# new.net
KiCad netlist of a schematic drawn in EAGLE
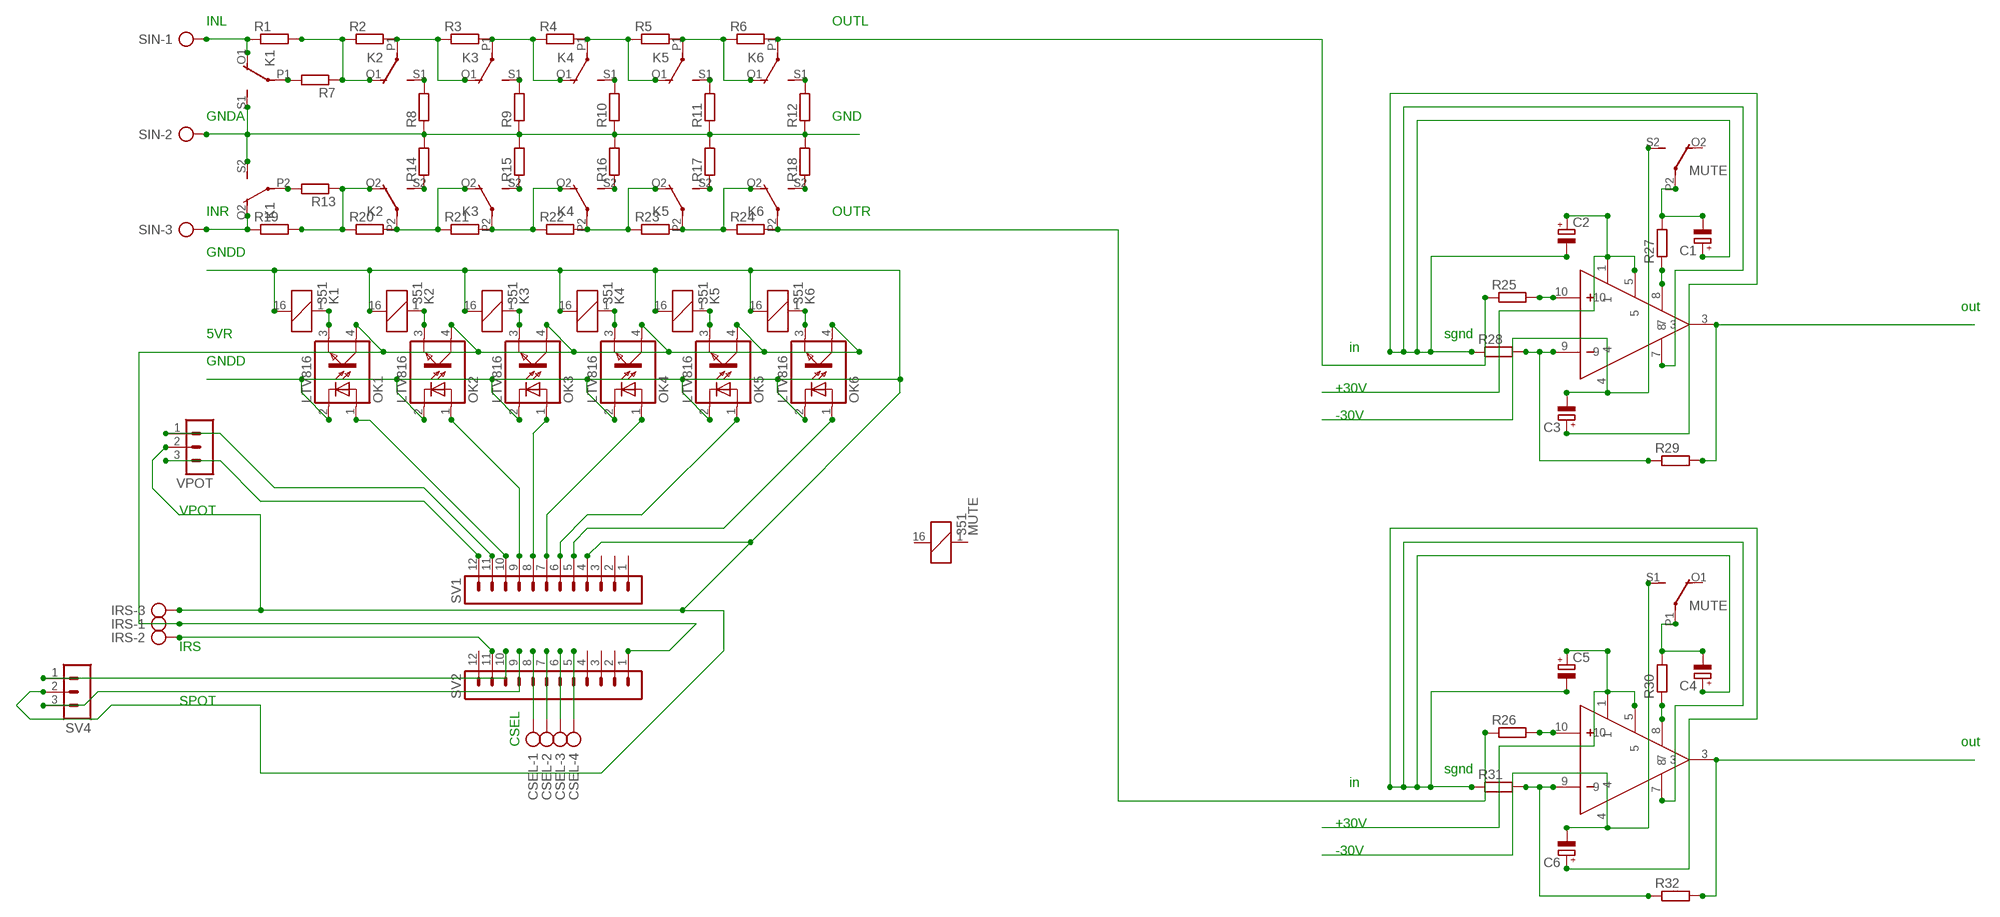
[diagram p0: schematic, sheet 1]

(export (version "E")
  (design (tool "Eeschema 10.0.6"))
  (components
    (comp (ref "C1")
      (value "CPOL-EUE5-13")
      (footprint "eagle-import:E5-13")
      (libsource (lib "eagle-import") (part "CPOL-EUE5-13"))
    )
    (comp (ref "C2")
      (value "CPOL-EUE5-13")
      (footprint "eagle-import:E5-13")
      (libsource (lib "eagle-import") (part "CPOL-EUE5-13"))
    )
    (comp (ref "C3")
      (value "CPOL-EUE5-13")
      (footprint "eagle-import:E5-13")
      (libsource (lib "eagle-import") (part "CPOL-EUE5-13"))
    )
    (comp (ref "C4")
      (value "CPOL-EUE5-13")
      (footprint "eagle-import:E5-13")
      (libsource (lib "eagle-import") (part "CPOL-EUE5-13"))
    )
    (comp (ref "C5")
      (value "CPOL-EUE5-13")
      (footprint "eagle-import:E5-13")
      (libsource (lib "eagle-import") (part "CPOL-EUE5-13"))
    )
    (comp (ref "C6")
      (value "CPOL-EUE5-13")
      (footprint "eagle-import:E5-13")
      (libsource (lib "eagle-import") (part "CPOL-EUE5-13"))
    )
    (comp (ref "CSEL")
      (value "AK500/4")
      (footprint "eagle-import:AK500_4")
      (libsource (lib "eagle-import") (part "AK500/4"))
    )
    (comp (ref "IRS")
      (value "AK500/3")
      (footprint "eagle-import:AK500_3")
      (libsource (lib "eagle-import") (part "AK500/3"))
    )
    (comp (ref "K1")
      (value "351")
      (footprint "eagle-import:351")
      (libsource (lib "eagle-import") (part "351"))
    )
    (comp (ref "K2")
      (value "351")
      (footprint "eagle-import:351")
      (libsource (lib "eagle-import") (part "351"))
    )
    (comp (ref "K3")
      (value "351")
      (footprint "eagle-import:351")
      (libsource (lib "eagle-import") (part "351"))
    )
    (comp (ref "K4")
      (value "351")
      (footprint "eagle-import:351")
      (libsource (lib "eagle-import") (part "351"))
    )
    (comp (ref "K5")
      (value "351")
      (footprint "eagle-import:351")
      (libsource (lib "eagle-import") (part "351"))
    )
    (comp (ref "K6")
      (value "351")
      (footprint "eagle-import:351")
      (libsource (lib "eagle-import") (part "351"))
    )
    (comp (ref "MUTE")
      (value "351")
      (footprint "eagle-import:351")
      (libsource (lib "eagle-import") (part "351"))
    )
    (comp (ref "OK1")
      (value "LTV816")
      (footprint "eagle-import:DIL04")
      (libsource (lib "eagle-import") (part "LTV816"))
    )
    (comp (ref "OK2")
      (value "LTV816")
      (footprint "eagle-import:DIL04")
      (libsource (lib "eagle-import") (part "LTV816"))
    )
    (comp (ref "OK3")
      (value "LTV816")
      (footprint "eagle-import:DIL04")
      (libsource (lib "eagle-import") (part "LTV816"))
    )
    (comp (ref "OK4")
      (value "LTV816")
      (footprint "eagle-import:DIL04")
      (libsource (lib "eagle-import") (part "LTV816"))
    )
    (comp (ref "OK5")
      (value "LTV816")
      (footprint "eagle-import:DIL04")
      (libsource (lib "eagle-import") (part "LTV816"))
    )
    (comp (ref "OK6")
      (value "LTV816")
      (footprint "eagle-import:DIL04")
      (libsource (lib "eagle-import") (part "LTV816"))
    )
    (comp (ref "R1")
      (value "R-EU_0204/7")
      (footprint "eagle-import:0204_7")
      (libsource (lib "eagle-import") (part "R-EU_0204/7"))
    )
    (comp (ref "R2")
      (value "R-EU_0204/7")
      (footprint "eagle-import:0204_7")
      (libsource (lib "eagle-import") (part "R-EU_0204/7"))
    )
    (comp (ref "R3")
      (value "R-EU_0204/7")
      (footprint "eagle-import:0204_7")
      (libsource (lib "eagle-import") (part "R-EU_0204/7"))
    )
    (comp (ref "R4")
      (value "R-EU_0204/7")
      (footprint "eagle-import:0204_7")
      (libsource (lib "eagle-import") (part "R-EU_0204/7"))
    )
    (comp (ref "R5")
      (value "R-EU_0204/7")
      (footprint "eagle-import:0204_7")
      (libsource (lib "eagle-import") (part "R-EU_0204/7"))
    )
    (comp (ref "R6")
      (value "R-EU_0204/7")
      (footprint "eagle-import:0204_7")
      (libsource (lib "eagle-import") (part "R-EU_0204/7"))
    )
    (comp (ref "R7")
      (value "R-EU_0204/7")
      (footprint "eagle-import:0204_7")
      (libsource (lib "eagle-import") (part "R-EU_0204/7"))
    )
    (comp (ref "R8")
      (value "R-EU_0204/7")
      (footprint "eagle-import:0204_7")
      (libsource (lib "eagle-import") (part "R-EU_0204/7"))
    )
    (comp (ref "R9")
      (value "R-EU_0204/7")
      (footprint "eagle-import:0204_7")
      (libsource (lib "eagle-import") (part "R-EU_0204/7"))
    )
    (comp (ref "R10")
      (value "R-EU_0204/7")
      (footprint "eagle-import:0204_7")
      (libsource (lib "eagle-import") (part "R-EU_0204/7"))
    )
    (comp (ref "R11")
      (value "R-EU_0204/7")
      (footprint "eagle-import:0204_7")
      (libsource (lib "eagle-import") (part "R-EU_0204/7"))
    )
    (comp (ref "R12")
      (value "R-EU_0204/7")
      (footprint "eagle-import:0204_7")
      (libsource (lib "eagle-import") (part "R-EU_0204/7"))
    )
    (comp (ref "R13")
      (value "R-EU_0204/7")
      (footprint "eagle-import:0204_7")
      (libsource (lib "eagle-import") (part "R-EU_0204/7"))
    )
    (comp (ref "R14")
      (value "R-EU_0204/7")
      (footprint "eagle-import:0204_7")
      (libsource (lib "eagle-import") (part "R-EU_0204/7"))
    )
    (comp (ref "R15")
      (value "R-EU_0204/7")
      (footprint "eagle-import:0204_7")
      (libsource (lib "eagle-import") (part "R-EU_0204/7"))
    )
    (comp (ref "R16")
      (value "R-EU_0204/7")
      (footprint "eagle-import:0204_7")
      (libsource (lib "eagle-import") (part "R-EU_0204/7"))
    )
    (comp (ref "R17")
      (value "R-EU_0204/7")
      (footprint "eagle-import:0204_7")
      (libsource (lib "eagle-import") (part "R-EU_0204/7"))
    )
    (comp (ref "R18")
      (value "R-EU_0204/7")
      (footprint "eagle-import:0204_7")
      (libsource (lib "eagle-import") (part "R-EU_0204/7"))
    )
    (comp (ref "R19")
      (value "R-EU_0204/7")
      (footprint "eagle-import:0204_7")
      (libsource (lib "eagle-import") (part "R-EU_0204/7"))
    )
    (comp (ref "R20")
      (value "R-EU_0204/7")
      (footprint "eagle-import:0204_7")
      (libsource (lib "eagle-import") (part "R-EU_0204/7"))
    )
    (comp (ref "R21")
      (value "R-EU_0204/7")
      (footprint "eagle-import:0204_7")
      (libsource (lib "eagle-import") (part "R-EU_0204/7"))
    )
    (comp (ref "R22")
      (value "R-EU_0204/7")
      (footprint "eagle-import:0204_7")
      (libsource (lib "eagle-import") (part "R-EU_0204/7"))
    )
    (comp (ref "R23")
      (value "R-EU_0204/7")
      (footprint "eagle-import:0204_7")
      (libsource (lib "eagle-import") (part "R-EU_0204/7"))
    )
    (comp (ref "R24")
      (value "R-EU_0204/7")
      (footprint "eagle-import:0204_7")
      (libsource (lib "eagle-import") (part "R-EU_0204/7"))
    )
    (comp (ref "R25")
      (value "R-EU_0207/10")
      (footprint "eagle-import:0207_10")
      (libsource (lib "eagle-import") (part "R-EU_0207/10"))
    )
    (comp (ref "R26")
      (value "R-EU_0207/10")
      (footprint "eagle-import:0207_10")
      (libsource (lib "eagle-import") (part "R-EU_0207/10"))
    )
    (comp (ref "R27")
      (value "R-EU_0207/10")
      (footprint "eagle-import:0207_10")
      (libsource (lib "eagle-import") (part "R-EU_0207/10"))
    )
    (comp (ref "R28")
      (value "R-EU_0207/10")
      (footprint "eagle-import:0207_10")
      (libsource (lib "eagle-import") (part "R-EU_0207/10"))
    )
    (comp (ref "R29")
      (value "R-EU_0207/10")
      (footprint "eagle-import:0207_10")
      (libsource (lib "eagle-import") (part "R-EU_0207/10"))
    )
    (comp (ref "R30")
      (value "R-EU_0207/10")
      (footprint "eagle-import:0207_10")
      (libsource (lib "eagle-import") (part "R-EU_0207/10"))
    )
    (comp (ref "R31")
      (value "R-EU_0207/10")
      (footprint "eagle-import:0207_10")
      (libsource (lib "eagle-import") (part "R-EU_0207/10"))
    )
    (comp (ref "R32")
      (value "R-EU_0207/10")
      (footprint "eagle-import:0207_10")
      (libsource (lib "eagle-import") (part "R-EU_0207/10"))
    )
    (comp (ref "SIN")
      (value "AK500/3")
      (footprint "eagle-import:AK500_3")
      (libsource (lib "eagle-import") (part "AK500/3"))
    )
    (comp (ref "SV1")
      (value "MA12-1")
      (footprint "eagle-import:MA12-1")
      (libsource (lib "eagle-import") (part "MA12-1"))
    )
    (comp (ref "SV2")
      (value "MA12-1")
      (footprint "eagle-import:MA12-1")
      (libsource (lib "eagle-import") (part "MA12-1"))
    )
    (comp (ref "SV4")
      (value "MA03-1")
      (footprint "eagle-import:MA03-1")
      (libsource (lib "eagle-import") (part "MA03-1"))
    )
    (comp (ref "U$1")
      (value "LM3886T")
      (footprint "eagle-import:TO220-11")
      (libsource (lib "eagle-import") (part "LM3886T"))
    )
    (comp (ref "U$2")
      (value "LM3886T")
      (footprint "eagle-import:TO220-11")
      (libsource (lib "eagle-import") (part "LM3886T"))
    )
    (comp (ref "VPOT")
      (value "MA03-1")
      (footprint "eagle-import:MA03-1")
      (libsource (lib "eagle-import") (part "MA03-1"))
    )
  )
  (nets
    (net (code "1") (name "/GNDA") (class "Default")
      (node (ref "C1") (pin "+") (pinfunction "+_+") (pintype "passive"))
      (node (ref "C2") (pin "-") (pinfunction "-_-") (pintype "passive"))
      (node (ref "C3") (pin "+") (pinfunction "+_+") (pintype "passive"))
      (node (ref "C4") (pin "+") (pinfunction "+_+") (pintype "passive"))
      (node (ref "C5") (pin "-") (pinfunction "-_-") (pintype "passive"))
      (node (ref "C6") (pin "+") (pinfunction "+_+") (pintype "passive"))
      (node (ref "K1") (pin "S1") (pinfunction "S_S1") (pintype "passive"))
      (node (ref "K1") (pin "S2") (pinfunction "S_S2") (pintype "passive"))
      (node (ref "R10") (pin "1") (pinfunction "1_1") (pintype "passive"))
      (node (ref "R11") (pin "1") (pinfunction "1_1") (pintype "passive"))
      (node (ref "R12") (pin "1") (pinfunction "1_1") (pintype "passive"))
      (node (ref "R14") (pin "2") (pinfunction "2_2") (pintype "passive"))
      (node (ref "R15") (pin "2") (pinfunction "2_2") (pintype "passive"))
      (node (ref "R16") (pin "2") (pinfunction "2_2") (pintype "passive"))
      (node (ref "R17") (pin "2") (pinfunction "2_2") (pintype "passive"))
      (node (ref "R18") (pin "2") (pinfunction "2_2") (pintype "passive"))
      (node (ref "R28") (pin "1") (pinfunction "1_1") (pintype "passive"))
      (node (ref "R31") (pin "1") (pinfunction "1_1") (pintype "passive"))
      (node (ref "R8") (pin "1") (pinfunction "1_1") (pintype "passive"))
      (node (ref "R9") (pin "1") (pinfunction "1_1") (pintype "passive"))
      (node (ref "SIN") (pin "2") (pinfunction "KL_2") (pintype "passive"))
      (node (ref "U$1") (pin "7") (pinfunction "7_7") (pintype "power_in"))
      (node (ref "U$2") (pin "7") (pinfunction "7_7") (pintype "power_in"))
    )
    (net (code "2") (name "Net-(C2-Pad+)") (class "Default")
      (node (ref "C2") (pin "+") (pinfunction "+_+") (pintype "passive"))
      (node (ref "U$1") (pin "1") (pinfunction "1_1") (pintype "power_in"))
      (node (ref "U$1") (pin "5") (pinfunction "5_5") (pintype "power_in"))
    )
    (net (code "3") (name "Net-(C5-Pad+)") (class "Default")
      (node (ref "C5") (pin "+") (pinfunction "+_+") (pintype "passive"))
      (node (ref "U$2") (pin "1") (pinfunction "1_1") (pintype "power_in"))
      (node (ref "U$2") (pin "5") (pinfunction "5_5") (pintype "power_in"))
    )
    (net (code "4") (name "Net-(CSELA-KL)") (class "Default")
      (node (ref "CSEL") (pin "1") (pinfunction "KL_1") (pintype "passive"))
      (node (ref "SV2") (pin "8") (pinfunction "8_8") (pintype "passive"))
    )
    (net (code "5") (name "Net-(CSELB-KL)") (class "Default")
      (node (ref "CSEL") (pin "2") (pinfunction "KL_2") (pintype "passive"))
      (node (ref "SV2") (pin "7") (pinfunction "7_7") (pintype "passive"))
    )
    (net (code "6") (name "Net-(CSELC-KL)") (class "Default")
      (node (ref "CSEL") (pin "3") (pinfunction "KL_3") (pintype "passive"))
      (node (ref "SV2") (pin "6") (pinfunction "6_6") (pintype "passive"))
    )
    (net (code "7") (name "Net-(CSELD-KL)") (class "Default")
      (node (ref "CSEL") (pin "4") (pinfunction "KL_4") (pintype "passive"))
      (node (ref "SV2") (pin "5") (pinfunction "5_5") (pintype "passive"))
    )
    (net (code "8") (name "Net-(IRSA-KL)") (class "Default")
      (node (ref "IRS") (pin "1") (pinfunction "KL_1") (pintype "passive"))
      (node (ref "OK1") (pin "4") (pinfunction "COL_4") (pintype "passive"))
      (node (ref "OK2") (pin "4") (pinfunction "COL_4") (pintype "passive"))
      (node (ref "OK3") (pin "4") (pinfunction "COL_4") (pintype "passive"))
      (node (ref "OK4") (pin "4") (pinfunction "COL_4") (pintype "passive"))
      (node (ref "OK5") (pin "4") (pinfunction "COL_4") (pintype "passive"))
      (node (ref "OK6") (pin "4") (pinfunction "COL_4") (pintype "passive"))
      (node (ref "SV2") (pin "1") (pinfunction "1_1") (pintype "passive"))
    )
    (net (code "9") (name "Net-(IRSB-KL)") (class "Default")
      (node (ref "IRS") (pin "2") (pinfunction "KL_2") (pintype "passive"))
      (node (ref "SV2") (pin "11") (pinfunction "11_11") (pintype "passive"))
    )
    (net (code "10") (name "Net-(IRSC-KL)") (class "Default")
      (node (ref "IRS") (pin "3") (pinfunction "KL_3") (pintype "passive"))
      (node (ref "K1") (pin "16") (pinfunction "2_16") (pintype "passive"))
      (node (ref "K2") (pin "16") (pinfunction "2_16") (pintype "passive"))
      (node (ref "K3") (pin "16") (pinfunction "2_16") (pintype "passive"))
      (node (ref "K4") (pin "16") (pinfunction "2_16") (pintype "passive"))
      (node (ref "K5") (pin "16") (pinfunction "2_16") (pintype "passive"))
      (node (ref "K6") (pin "16") (pinfunction "2_16") (pintype "passive"))
      (node (ref "OK1") (pin "2") (pinfunction "C_2") (pintype "passive"))
      (node (ref "OK2") (pin "2") (pinfunction "C_2") (pintype "passive"))
      (node (ref "OK3") (pin "2") (pinfunction "C_2") (pintype "passive"))
      (node (ref "OK4") (pin "2") (pinfunction "C_2") (pintype "passive"))
      (node (ref "OK5") (pin "2") (pinfunction "C_2") (pintype "passive"))
      (node (ref "OK6") (pin "2") (pinfunction "C_2") (pintype "passive"))
      (node (ref "SV1") (pin "4") (pinfunction "4_4") (pintype "passive"))
      (node (ref "SV4") (pin "2") (pinfunction "2_2") (pintype "passive"))
      (node (ref "VPOT") (pin "2") (pinfunction "2_2") (pintype "passive"))
    )
    (net (code "11") (name "Net-(K1B-O)") (class "Default")
      (node (ref "K1") (pin "O1") (pinfunction "O_O1") (pintype "passive"))
      (node (ref "R1") (pin "1") (pinfunction "1_1") (pintype "passive"))
      (node (ref "SIN") (pin "1") (pinfunction "KL_1") (pintype "passive"))
    )
    (net (code "12") (name "Net-(K1B-P)") (class "Default")
      (node (ref "K1") (pin "P1") (pinfunction "P_P1") (pintype "passive"))
      (node (ref "R7") (pin "2") (pinfunction "2_2") (pintype "passive"))
    )
    (net (code "13") (name "Net-(K1C-O)") (class "Default")
      (node (ref "K1") (pin "O2") (pinfunction "O_O2") (pintype "passive"))
      (node (ref "R19") (pin "1") (pinfunction "1_1") (pintype "passive"))
      (node (ref "SIN") (pin "3") (pinfunction "KL_3") (pintype "passive"))
    )
    (net (code "14") (name "Net-(K1C-P)") (class "Default")
      (node (ref "K1") (pin "P2") (pinfunction "P_P2") (pintype "passive"))
      (node (ref "R13") (pin "2") (pinfunction "2_2") (pintype "passive"))
    )
    (net (code "15") (name "Net-(K2B-O)") (class "Default")
      (node (ref "K2") (pin "O1") (pinfunction "O_O1") (pintype "passive"))
      (node (ref "R1") (pin "2") (pinfunction "2_2") (pintype "passive"))
      (node (ref "R2") (pin "1") (pinfunction "1_1") (pintype "passive"))
      (node (ref "R7") (pin "1") (pinfunction "1_1") (pintype "passive"))
    )
    (net (code "16") (name "Net-(K2B-P)") (class "Default")
      (node (ref "K2") (pin "P1") (pinfunction "P_P1") (pintype "passive"))
      (node (ref "K3") (pin "O1") (pinfunction "O_O1") (pintype "passive"))
      (node (ref "R2") (pin "2") (pinfunction "2_2") (pintype "passive"))
      (node (ref "R3") (pin "1") (pinfunction "1_1") (pintype "passive"))
    )
    (net (code "17") (name "Net-(K2B-S)") (class "Default")
      (node (ref "K2") (pin "S1") (pinfunction "S_S1") (pintype "passive"))
      (node (ref "R8") (pin "2") (pinfunction "2_2") (pintype "passive"))
    )
    (net (code "18") (name "Net-(K2C-O)") (class "Default")
      (node (ref "K2") (pin "O2") (pinfunction "O_O2") (pintype "passive"))
      (node (ref "R13") (pin "1") (pinfunction "1_1") (pintype "passive"))
      (node (ref "R19") (pin "2") (pinfunction "2_2") (pintype "passive"))
      (node (ref "R20") (pin "1") (pinfunction "1_1") (pintype "passive"))
    )
    (net (code "19") (name "Net-(K2C-P)") (class "Default")
      (node (ref "K2") (pin "P2") (pinfunction "P_P2") (pintype "passive"))
      (node (ref "K3") (pin "O2") (pinfunction "O_O2") (pintype "passive"))
      (node (ref "R20") (pin "2") (pinfunction "2_2") (pintype "passive"))
      (node (ref "R21") (pin "1") (pinfunction "1_1") (pintype "passive"))
    )
    (net (code "20") (name "Net-(K2C-S)") (class "Default")
      (node (ref "K2") (pin "S2") (pinfunction "S_S2") (pintype "passive"))
      (node (ref "R14") (pin "1") (pinfunction "1_1") (pintype "passive"))
    )
    (net (code "21") (name "Net-(K3B-P)") (class "Default")
      (node (ref "K3") (pin "P1") (pinfunction "P_P1") (pintype "passive"))
      (node (ref "K4") (pin "O1") (pinfunction "O_O1") (pintype "passive"))
      (node (ref "R3") (pin "2") (pinfunction "2_2") (pintype "passive"))
      (node (ref "R4") (pin "1") (pinfunction "1_1") (pintype "passive"))
    )
    (net (code "22") (name "Net-(K3B-S)") (class "Default")
      (node (ref "K3") (pin "S1") (pinfunction "S_S1") (pintype "passive"))
      (node (ref "R9") (pin "2") (pinfunction "2_2") (pintype "passive"))
    )
    (net (code "23") (name "Net-(K3C-P)") (class "Default")
      (node (ref "K3") (pin "P2") (pinfunction "P_P2") (pintype "passive"))
      (node (ref "K4") (pin "O2") (pinfunction "O_O2") (pintype "passive"))
      (node (ref "R21") (pin "2") (pinfunction "2_2") (pintype "passive"))
      (node (ref "R22") (pin "1") (pinfunction "1_1") (pintype "passive"))
    )
    (net (code "24") (name "Net-(K3C-S)") (class "Default")
      (node (ref "K3") (pin "S2") (pinfunction "S_S2") (pintype "passive"))
      (node (ref "R15") (pin "1") (pinfunction "1_1") (pintype "passive"))
    )
    (net (code "25") (name "Net-(K4B-P)") (class "Default")
      (node (ref "K4") (pin "P1") (pinfunction "P_P1") (pintype "passive"))
      (node (ref "K5") (pin "O1") (pinfunction "O_O1") (pintype "passive"))
      (node (ref "R4") (pin "2") (pinfunction "2_2") (pintype "passive"))
      (node (ref "R5") (pin "1") (pinfunction "1_1") (pintype "passive"))
    )
    (net (code "26") (name "Net-(K4B-S)") (class "Default")
      (node (ref "K4") (pin "S1") (pinfunction "S_S1") (pintype "passive"))
      (node (ref "R10") (pin "2") (pinfunction "2_2") (pintype "passive"))
    )
    (net (code "27") (name "Net-(K4C-P)") (class "Default")
      (node (ref "K4") (pin "P2") (pinfunction "P_P2") (pintype "passive"))
      (node (ref "K5") (pin "O2") (pinfunction "O_O2") (pintype "passive"))
      (node (ref "R22") (pin "2") (pinfunction "2_2") (pintype "passive"))
      (node (ref "R23") (pin "1") (pinfunction "1_1") (pintype "passive"))
    )
    (net (code "28") (name "Net-(K4C-S)") (class "Default")
      (node (ref "K4") (pin "S2") (pinfunction "S_S2") (pintype "passive"))
      (node (ref "R16") (pin "1") (pinfunction "1_1") (pintype "passive"))
    )
    (net (code "29") (name "Net-(K5B-P)") (class "Default")
      (node (ref "K5") (pin "P1") (pinfunction "P_P1") (pintype "passive"))
      (node (ref "K6") (pin "O1") (pinfunction "O_O1") (pintype "passive"))
      (node (ref "R5") (pin "2") (pinfunction "2_2") (pintype "passive"))
      (node (ref "R6") (pin "1") (pinfunction "1_1") (pintype "passive"))
    )
    (net (code "30") (name "Net-(K5B-S)") (class "Default")
      (node (ref "K5") (pin "S1") (pinfunction "S_S1") (pintype "passive"))
      (node (ref "R11") (pin "2") (pinfunction "2_2") (pintype "passive"))
    )
    (net (code "31") (name "Net-(K5C-P)") (class "Default")
      (node (ref "K5") (pin "P2") (pinfunction "P_P2") (pintype "passive"))
      (node (ref "K6") (pin "O2") (pinfunction "O_O2") (pintype "passive"))
      (node (ref "R23") (pin "2") (pinfunction "2_2") (pintype "passive"))
      (node (ref "R24") (pin "1") (pinfunction "1_1") (pintype "passive"))
    )
    (net (code "32") (name "Net-(K5C-S)") (class "Default")
      (node (ref "K5") (pin "S2") (pinfunction "S_S2") (pintype "passive"))
      (node (ref "R17") (pin "1") (pinfunction "1_1") (pintype "passive"))
    )
    (net (code "33") (name "Net-(K6B-P)") (class "Default")
      (node (ref "K6") (pin "P1") (pinfunction "P_P1") (pintype "passive"))
      (node (ref "R25") (pin "1") (pinfunction "1_1") (pintype "passive"))
      (node (ref "R6") (pin "2") (pinfunction "2_2") (pintype "passive"))
    )
    (net (code "34") (name "Net-(K6B-S)") (class "Default")
      (node (ref "K6") (pin "S1") (pinfunction "S_S1") (pintype "passive"))
      (node (ref "R12") (pin "2") (pinfunction "2_2") (pintype "passive"))
    )
    (net (code "35") (name "Net-(K6C-P)") (class "Default")
      (node (ref "K6") (pin "P2") (pinfunction "P_P2") (pintype "passive"))
      (node (ref "R24") (pin "2") (pinfunction "2_2") (pintype "passive"))
      (node (ref "R26") (pin "1") (pinfunction "1_1") (pintype "passive"))
    )
    (net (code "36") (name "Net-(K6C-S)") (class "Default")
      (node (ref "K6") (pin "S2") (pinfunction "S_S2") (pintype "passive"))
      (node (ref "R18") (pin "1") (pinfunction "1_1") (pintype "passive"))
    )
    (net (code "37") (name "Net-(MUTEB-P)") (class "Default")
      (node (ref "C4") (pin "-") (pinfunction "-_-") (pintype "passive"))
      (node (ref "MUTE") (pin "P1") (pinfunction "P_P1") (pintype "passive"))
      (node (ref "R30") (pin "2") (pinfunction "2_2") (pintype "passive"))
    )
    (net (code "38") (name "Net-(MUTEB-S)") (class "Default")
      (node (ref "C6") (pin "-") (pinfunction "-_-") (pintype "passive"))
      (node (ref "MUTE") (pin "S1") (pinfunction "S_S1") (pintype "passive"))
      (node (ref "U$2") (pin "4") (pinfunction "4_4") (pintype "power_in"))
    )
    (net (code "39") (name "Net-(MUTEC-P)") (class "Default")
      (node (ref "C1") (pin "-") (pinfunction "-_-") (pintype "passive"))
      (node (ref "MUTE") (pin "P2") (pinfunction "P_P2") (pintype "passive"))
      (node (ref "R27") (pin "2") (pinfunction "2_2") (pintype "passive"))
    )
    (net (code "40") (name "Net-(MUTEC-S)") (class "Default")
      (node (ref "C3") (pin "-") (pinfunction "-_-") (pintype "passive"))
      (node (ref "MUTE") (pin "S2") (pinfunction "S_S2") (pintype "passive"))
      (node (ref "U$1") (pin "4") (pinfunction "4_4") (pintype "power_in"))
    )
    (net (code "41") (name "Net-(OK1-A)") (class "Default")
      (node (ref "OK1") (pin "1") (pinfunction "A_1") (pintype "passive"))
      (node (ref "SV1") (pin "10") (pinfunction "10_10") (pintype "passive"))
    )
    (net (code "42") (name "Net-(OK1-EMIT)") (class "Default")
      (node (ref "K1") (pin "1") (pinfunction "1_1") (pintype "passive"))
      (node (ref "OK1") (pin "3") (pinfunction "EMIT_3") (pintype "passive"))
    )
    (net (code "43") (name "Net-(OK2-A)") (class "Default")
      (node (ref "OK2") (pin "1") (pinfunction "A_1") (pintype "passive"))
      (node (ref "SV1") (pin "9") (pinfunction "9_9") (pintype "passive"))
    )
    (net (code "44") (name "Net-(OK2-EMIT)") (class "Default")
      (node (ref "K2") (pin "1") (pinfunction "1_1") (pintype "passive"))
      (node (ref "OK2") (pin "3") (pinfunction "EMIT_3") (pintype "passive"))
    )
    (net (code "45") (name "Net-(OK3-A)") (class "Default")
      (node (ref "OK3") (pin "1") (pinfunction "A_1") (pintype "passive"))
      (node (ref "SV1") (pin "8") (pinfunction "8_8") (pintype "passive"))
    )
    (net (code "46") (name "Net-(OK3-EMIT)") (class "Default")
      (node (ref "K3") (pin "1") (pinfunction "1_1") (pintype "passive"))
      (node (ref "OK3") (pin "3") (pinfunction "EMIT_3") (pintype "passive"))
    )
    (net (code "47") (name "Net-(OK4-A)") (class "Default")
      (node (ref "OK4") (pin "1") (pinfunction "A_1") (pintype "passive"))
      (node (ref "SV1") (pin "7") (pinfunction "7_7") (pintype "passive"))
    )
    (net (code "48") (name "Net-(OK4-EMIT)") (class "Default")
      (node (ref "K4") (pin "1") (pinfunction "1_1") (pintype "passive"))
      (node (ref "OK4") (pin "3") (pinfunction "EMIT_3") (pintype "passive"))
    )
    (net (code "49") (name "Net-(OK5-A)") (class "Default")
      (node (ref "OK5") (pin "1") (pinfunction "A_1") (pintype "passive"))
      (node (ref "SV1") (pin "6") (pinfunction "6_6") (pintype "passive"))
    )
    (net (code "50") (name "Net-(OK5-EMIT)") (class "Default")
      (node (ref "K5") (pin "1") (pinfunction "1_1") (pintype "passive"))
      (node (ref "OK5") (pin "3") (pinfunction "EMIT_3") (pintype "passive"))
    )
    (net (code "51") (name "Net-(OK6-A)") (class "Default")
      (node (ref "OK6") (pin "1") (pinfunction "A_1") (pintype "passive"))
      (node (ref "SV1") (pin "5") (pinfunction "5_5") (pintype "passive"))
    )
    (net (code "52") (name "Net-(OK6-EMIT)") (class "Default")
      (node (ref "K6") (pin "1") (pinfunction "1_1") (pintype "passive"))
      (node (ref "OK6") (pin "3") (pinfunction "EMIT_3") (pintype "passive"))
    )
    (net (code "53") (name "Net-(R25-Pad2)") (class "Default")
      (node (ref "R25") (pin "2") (pinfunction "2_2") (pintype "passive"))
      (node (ref "U$1") (pin "10") (pinfunction "10_10") (pintype "input"))
    )
    (net (code "54") (name "Net-(R26-Pad2)") (class "Default")
      (node (ref "R26") (pin "2") (pinfunction "2_2") (pintype "passive"))
      (node (ref "U$2") (pin "10") (pinfunction "10_10") (pintype "input"))
    )
    (net (code "55") (name "Net-(R27-Pad1)") (class "Default")
      (node (ref "R27") (pin "1") (pinfunction "1_1") (pintype "passive"))
      (node (ref "U$1") (pin "8") (pinfunction "8_8") (pintype "input"))
    )
    (net (code "56") (name "Net-(R28-Pad2)") (class "Default")
      (node (ref "R28") (pin "2") (pinfunction "2_2") (pintype "passive"))
      (node (ref "R29") (pin "1") (pinfunction "1_1") (pintype "passive"))
      (node (ref "U$1") (pin "9") (pinfunction "9_9") (pintype "input"))
    )
    (net (code "57") (name "Net-(R29-Pad2)") (class "Default")
      (node (ref "R29") (pin "2") (pinfunction "2_2") (pintype "passive"))
      (node (ref "U$1") (pin "3") (pinfunction "3_3") (pintype "output"))
    )
    (net (code "58") (name "Net-(R30-Pad1)") (class "Default")
      (node (ref "R30") (pin "1") (pinfunction "1_1") (pintype "passive"))
      (node (ref "U$2") (pin "8") (pinfunction "8_8") (pintype "input"))
    )
    (net (code "59") (name "Net-(R31-Pad2)") (class "Default")
      (node (ref "R31") (pin "2") (pinfunction "2_2") (pintype "passive"))
      (node (ref "R32") (pin "1") (pinfunction "1_1") (pintype "passive"))
      (node (ref "U$2") (pin "9") (pinfunction "9_9") (pintype "input"))
    )
    (net (code "60") (name "Net-(R32-Pad2)") (class "Default")
      (node (ref "R32") (pin "2") (pinfunction "2_2") (pintype "passive"))
      (node (ref "U$2") (pin "3") (pinfunction "3_3") (pintype "output"))
    )
    (net (code "61") (name "Net-(SV1-Pad11)") (class "Default")
      (node (ref "SV1") (pin "11") (pinfunction "11_11") (pintype "passive"))
      (node (ref "VPOT") (pin "1") (pinfunction "1_1") (pintype "passive"))
    )
    (net (code "62") (name "Net-(SV1-Pad12)") (class "Default")
      (node (ref "SV1") (pin "12") (pinfunction "12_12") (pintype "passive"))
      (node (ref "VPOT") (pin "3") (pinfunction "3_3") (pintype "passive"))
    )
    (net (code "63") (name "Net-(SV2-Pad9)") (class "Default")
      (node (ref "SV2") (pin "9") (pinfunction "9_9") (pintype "passive"))
      (node (ref "SV4") (pin "3") (pinfunction "3_3") (pintype "passive"))
    )
    (net (code "64") (name "Net-(SV2-Pad10)") (class "Default")
      (node (ref "SV2") (pin "10") (pinfunction "10_10") (pintype "passive"))
      (node (ref "SV4") (pin "1") (pinfunction "1_1") (pintype "passive"))
    )
    (net (code "65") (name "unconnected-(MUTE-Pad1)") (class "Default")
      (node (ref "MUTE") (pin "1") (pinfunction "1_1") (pintype "passive"))
    )
    (net (code "66") (name "unconnected-(MUTEA-2-Pad16)") (class "Default")
      (node (ref "MUTE") (pin "16") (pinfunction "2_16") (pintype "passive"))
    )
    (net (code "67") (name "unconnected-(MUTEB-O-PadO1)") (class "Default")
      (node (ref "MUTE") (pin "O1") (pinfunction "O_O1") (pintype "passive"))
    )
    (net (code "68") (name "unconnected-(MUTEC-O-PadO2)") (class "Default")
      (node (ref "MUTE") (pin "O2") (pinfunction "O_O2") (pintype "passive"))
    )
    (net (code "69") (name "unconnected-(SV1-Pad1)") (class "Default")
      (node (ref "SV1") (pin "1") (pinfunction "1_1") (pintype "passive"))
    )
    (net (code "70") (name "unconnected-(SV1-Pad2)") (class "Default")
      (node (ref "SV1") (pin "2") (pinfunction "2_2") (pintype "passive"))
    )
    (net (code "71") (name "unconnected-(SV1-Pad3)") (class "Default")
      (node (ref "SV1") (pin "3") (pinfunction "3_3") (pintype "passive"))
    )
    (net (code "72") (name "unconnected-(SV2-Pad2)") (class "Default")
      (node (ref "SV2") (pin "2") (pinfunction "2_2") (pintype "passive"))
    )
    (net (code "73") (name "unconnected-(SV2-Pad3)") (class "Default")
      (node (ref "SV2") (pin "3") (pinfunction "3_3") (pintype "passive"))
    )
    (net (code "74") (name "unconnected-(SV2-Pad4)") (class "Default")
      (node (ref "SV2") (pin "4") (pinfunction "4_4") (pintype "passive"))
    )
    (net (code "75") (name "unconnected-(SV2-Pad12)") (class "Default")
      (node (ref "SV2") (pin "12") (pinfunction "12_12") (pintype "passive"))
    )
  )
)
